# YMH01x.net
KiCad netlist of a schematic drawn in EAGLE
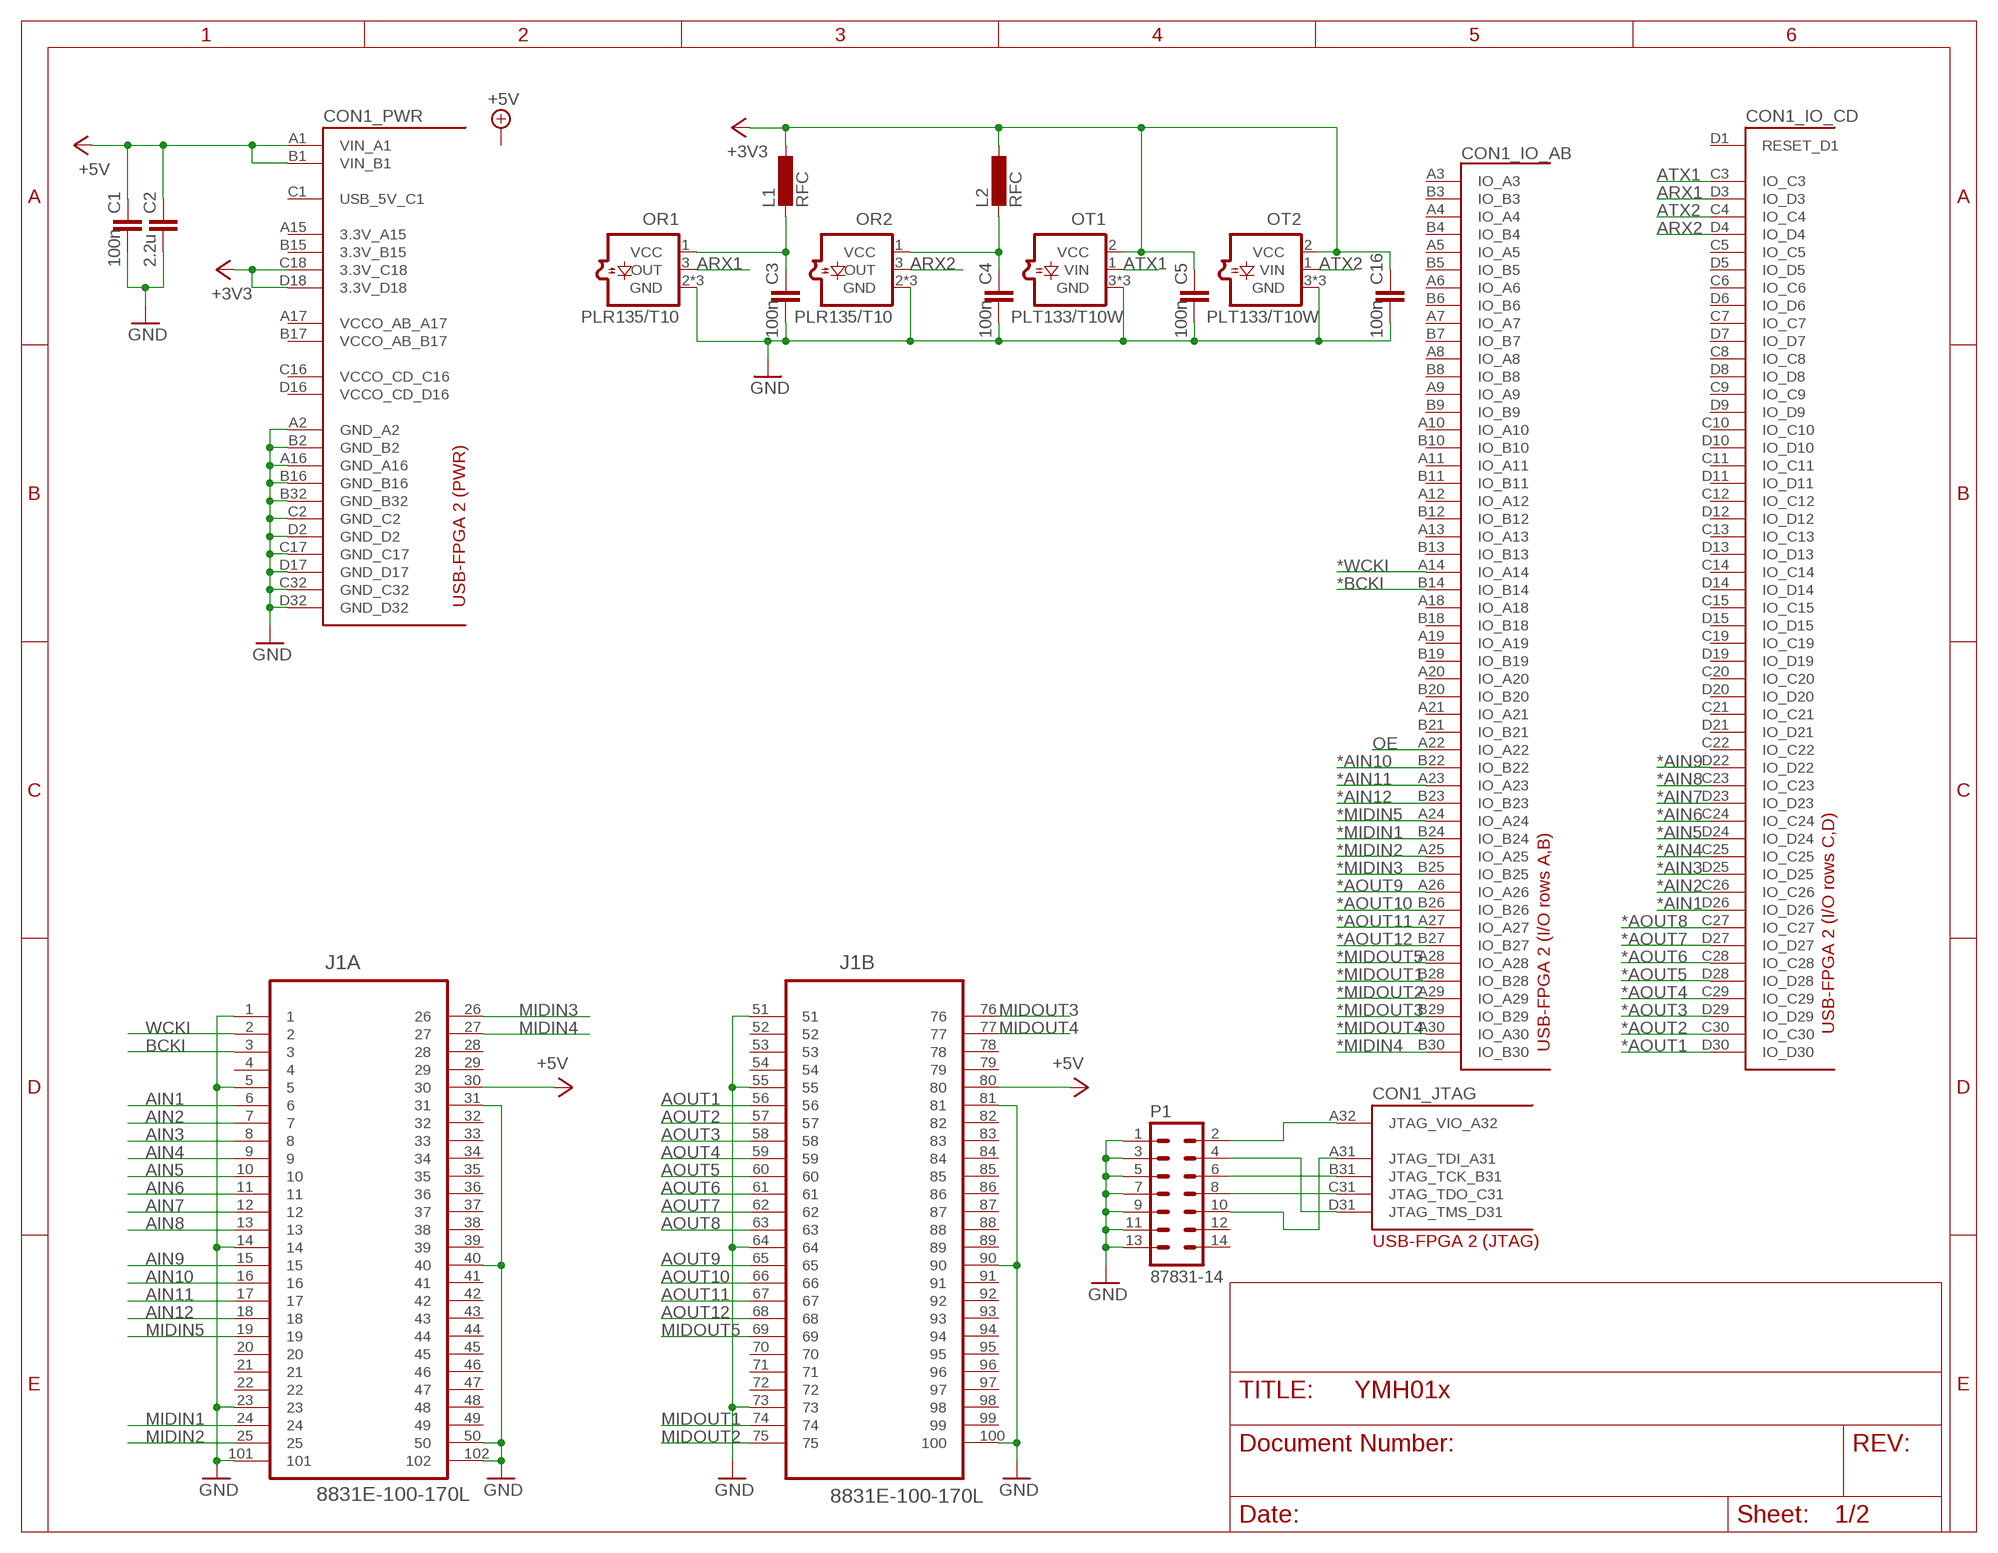
[diagram p0: schematic, sheet 1]
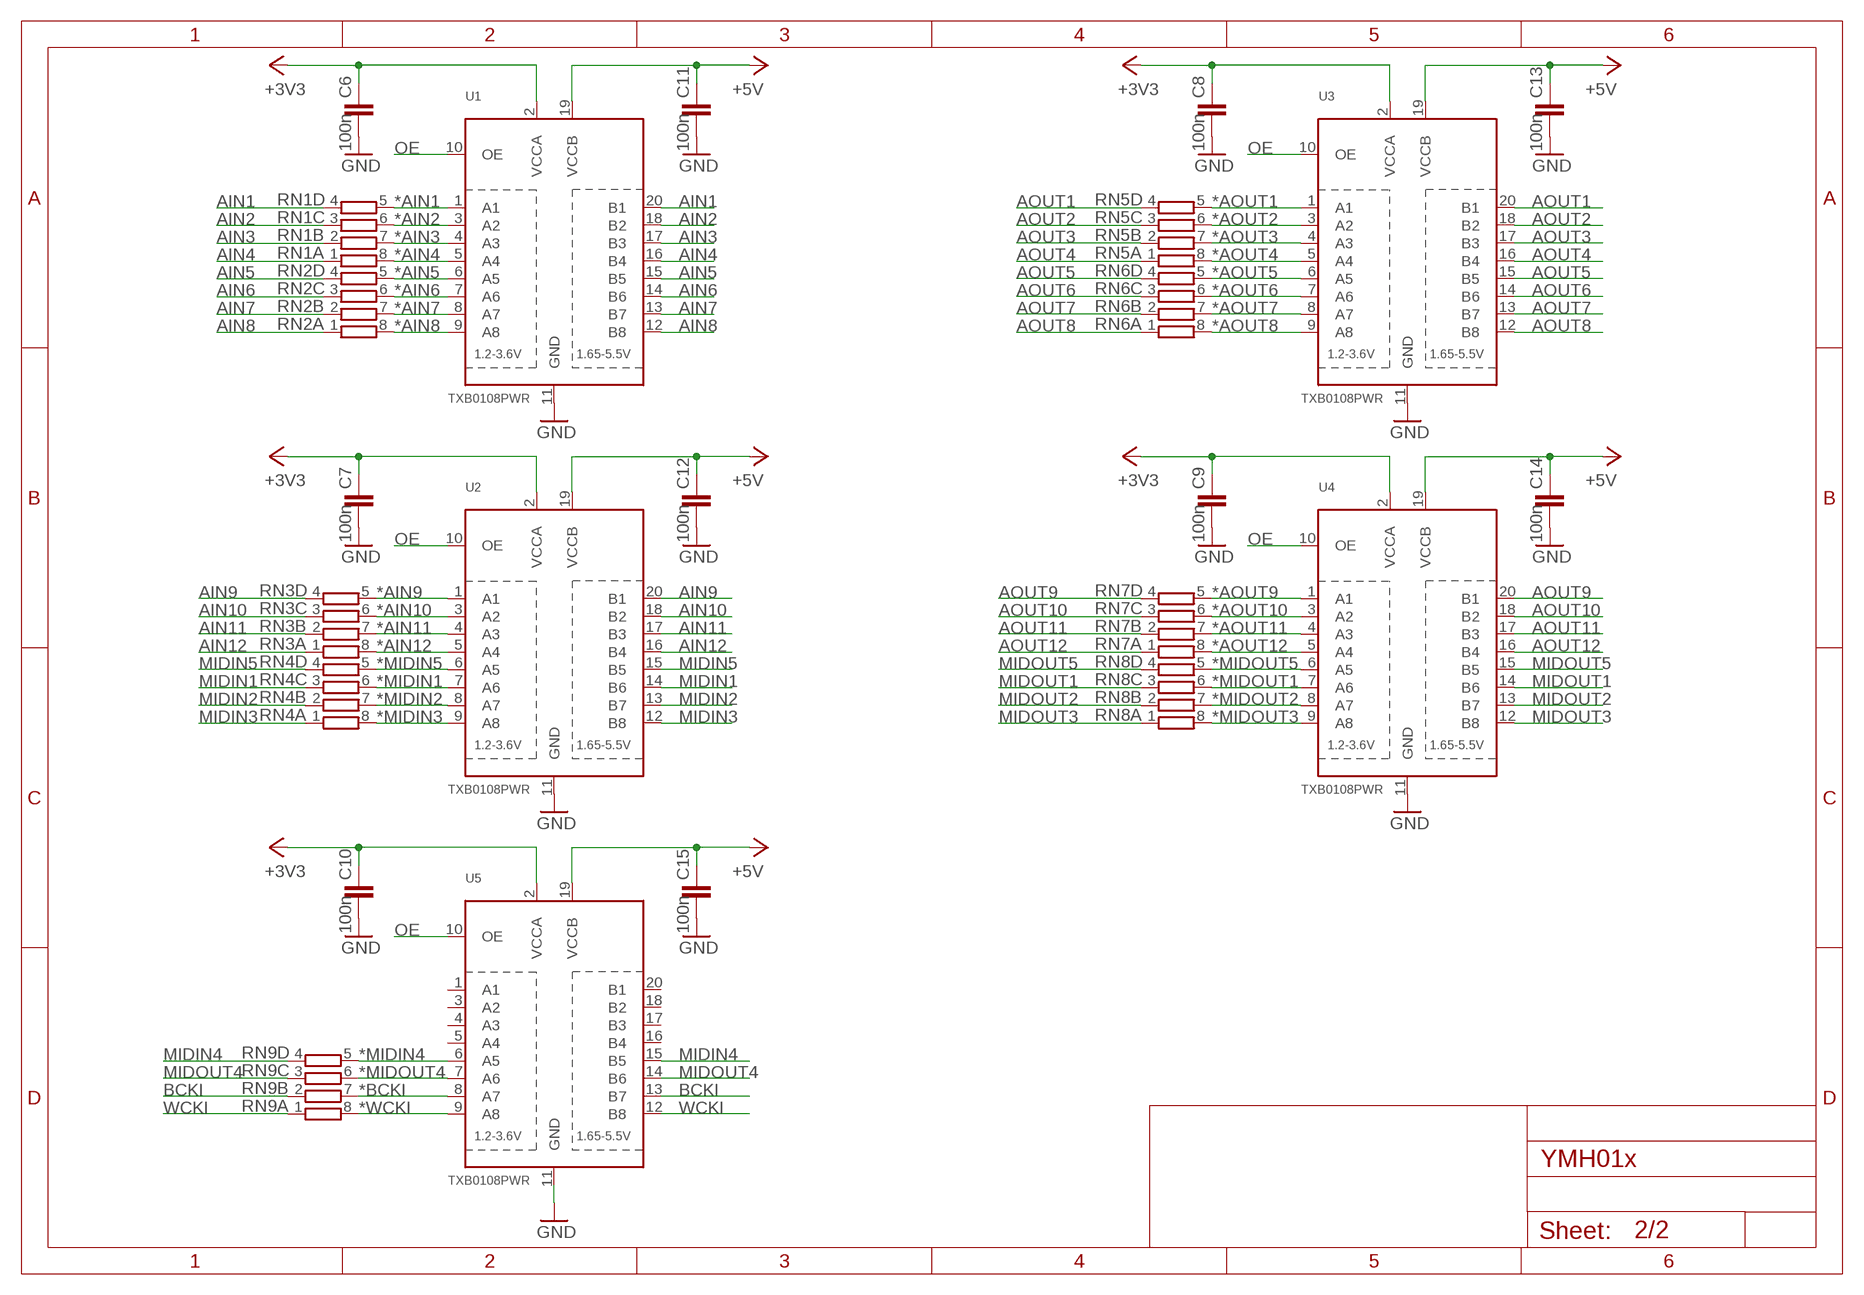
[diagram p1: schematic, sheet 2]

(export (version "E")
  (design (tool "Eeschema 10.0.6"))
  (components
    (comp (ref "C1")
      (value "100n")
      (footprint "eagle-import:C0603")
      (libsource (lib "eagle-import") (part "C-EUC0603"))
    )
    (comp (ref "C2")
      (value "2.2u")
      (footprint "eagle-import:C0603")
      (libsource (lib "eagle-import") (part "C-EUC0603"))
    )
    (comp (ref "C3")
      (value "100n")
      (footprint "eagle-import:C0603")
      (libsource (lib "eagle-import") (part "C-EUC0603"))
    )
    (comp (ref "C4")
      (value "100n")
      (footprint "eagle-import:C0603")
      (libsource (lib "eagle-import") (part "C-EUC0603"))
    )
    (comp (ref "C5")
      (value "100n")
      (footprint "eagle-import:C0603")
      (libsource (lib "eagle-import") (part "C-EUC0603"))
    )
    (comp (ref "C16")
      (value "100n")
      (footprint "eagle-import:C0603")
      (libsource (lib "eagle-import") (part "C-EUC0603"))
    )
    (comp (ref "CON1")
      (value "USB-FPGA-2THT")
      (footprint "eagle-import:USB-FPGA-2-THT")
      (libsource (lib "eagle-import") (part "USB-FPGA-2THT"))
    )
    (comp (ref "J1")
      (value "8831E-100-170L")
      (footprint "eagle-import:KEL_8831E-100-170L")
      (fields (field (name "MPN") "KEL_8831E-100-170L"))
      (libsource (lib "eagle-import") (part "8831E-100-170L"))
    )
    (comp (ref "L1")
      (value "RFC")
      (footprint "eagle-import:L2012C")
      (libsource (lib "eagle-import") (part "L-EUL2012C"))
    )
    (comp (ref "L2")
      (value "RFC")
      (footprint "eagle-import:L2012C")
      (libsource (lib "eagle-import") (part "L-EUL2012C"))
    )
    (comp (ref "OR1")
      (value "PLR135/T10")
      (footprint "eagle-import:PLR135_T10")
      (libsource (lib "eagle-import") (part "PLR135/T10"))
    )
    (comp (ref "OR2")
      (value "PLR135/T10")
      (footprint "eagle-import:PLR135_T10")
      (libsource (lib "eagle-import") (part "PLR135/T10"))
    )
    (comp (ref "OT1")
      (value "PLT133/T10W")
      (footprint "eagle-import:PLT133_T10")
      (libsource (lib "eagle-import") (part "PLT133/T10W"))
    )
    (comp (ref "OT2")
      (value "PLT133/T10W")
      (footprint "eagle-import:PLT133_T10")
      (libsource (lib "eagle-import") (part "PLT133/T10W"))
    )
    (comp (ref "P1")
      (value "87831-14")
      (footprint "eagle-import:87831-14")
      (libsource (lib "eagle-import") (part "87831-14"))
    )
    (comp (ref "C6")
      (value "100n")
      (footprint "eagle-import:C0603")
      (libsource (lib "eagle-import") (part "C-EUC0603"))
    )
    (comp (ref "C7")
      (value "100n")
      (footprint "eagle-import:C0603")
      (libsource (lib "eagle-import") (part "C-EUC0603"))
    )
    (comp (ref "C8")
      (value "100n")
      (footprint "eagle-import:C0603")
      (libsource (lib "eagle-import") (part "C-EUC0603"))
    )
    (comp (ref "C9")
      (value "100n")
      (footprint "eagle-import:C0603")
      (libsource (lib "eagle-import") (part "C-EUC0603"))
    )
    (comp (ref "C10")
      (value "100n")
      (footprint "eagle-import:C0603")
      (libsource (lib "eagle-import") (part "C-EUC0603"))
    )
    (comp (ref "C11")
      (value "100n")
      (footprint "eagle-import:C0603")
      (libsource (lib "eagle-import") (part "C-EUC0603"))
    )
    (comp (ref "C12")
      (value "100n")
      (footprint "eagle-import:C0603")
      (libsource (lib "eagle-import") (part "C-EUC0603"))
    )
    (comp (ref "C13")
      (value "100n")
      (footprint "eagle-import:C0603")
      (libsource (lib "eagle-import") (part "C-EUC0603"))
    )
    (comp (ref "C14")
      (value "100n")
      (footprint "eagle-import:C0603")
      (libsource (lib "eagle-import") (part "C-EUC0603"))
    )
    (comp (ref "C15")
      (value "100n")
      (footprint "eagle-import:C0603")
      (libsource (lib "eagle-import") (part "C-EUC0603"))
    )
    (comp (ref "RN1")
      (value "4R-N0603-ARC")
      (footprint "eagle-import:0603-ARC")
      (libsource (lib "eagle-import") (part "4R-N0603-ARC"))
    )
    (comp (ref "RN2")
      (value "4R-N0603-ARC")
      (footprint "eagle-import:0603-ARC")
      (libsource (lib "eagle-import") (part "4R-N0603-ARC"))
    )
    (comp (ref "RN3")
      (value "4R-N0603-ARC")
      (footprint "eagle-import:0603-ARC")
      (libsource (lib "eagle-import") (part "4R-N0603-ARC"))
    )
    (comp (ref "RN4")
      (value "4R-N0603-ARC")
      (footprint "eagle-import:0603-ARC")
      (libsource (lib "eagle-import") (part "4R-N0603-ARC"))
    )
    (comp (ref "RN5")
      (value "4R-N0603-ARC")
      (footprint "eagle-import:0603-ARC")
      (libsource (lib "eagle-import") (part "4R-N0603-ARC"))
    )
    (comp (ref "RN6")
      (value "4R-N0603-ARC")
      (footprint "eagle-import:0603-ARC")
      (libsource (lib "eagle-import") (part "4R-N0603-ARC"))
    )
    (comp (ref "RN7")
      (value "4R-N0603-ARC")
      (footprint "eagle-import:0603-ARC")
      (libsource (lib "eagle-import") (part "4R-N0603-ARC"))
    )
    (comp (ref "RN8")
      (value "4R-N0603-ARC")
      (footprint "eagle-import:0603-ARC")
      (libsource (lib "eagle-import") (part "4R-N0603-ARC"))
    )
    (comp (ref "RN9")
      (value "4R-N0603-ARC")
      (footprint "eagle-import:0603-ARC")
      (libsource (lib "eagle-import") (part "4R-N0603-ARC"))
    )
    (comp (ref "U1")
      (value "TXB0108PWR")
      (footprint "eagle-import:TSSOP20")
      (libsource (lib "eagle-import") (part "TXB0108PWR"))
    )
    (comp (ref "U2")
      (value "TXB0108PWR")
      (footprint "eagle-import:TSSOP20")
      (libsource (lib "eagle-import") (part "TXB0108PWR"))
    )
    (comp (ref "U3")
      (value "TXB0108PWR")
      (footprint "eagle-import:TSSOP20")
      (libsource (lib "eagle-import") (part "TXB0108PWR"))
    )
    (comp (ref "U4")
      (value "TXB0108PWR")
      (footprint "eagle-import:TSSOP20")
      (libsource (lib "eagle-import") (part "TXB0108PWR"))
    )
    (comp (ref "U5")
      (value "TXB0108PWR")
      (footprint "eagle-import:TSSOP20")
      (libsource (lib "eagle-import") (part "TXB0108PWR"))
    )
  )
  (nets
    (net (code "1") (name "*AIN1") (class "Default")
      (node (ref "CON1") (pin "D26") (pinfunction "IO_D26_D26") (pintype "bidirectional"))
      (node (ref "RN1") (pin "5") (pinfunction "2_5") (pintype "passive"))
      (node (ref "U1") (pin "1") (pinfunction "A1_1") (pintype "bidirectional"))
    )
    (net (code "2") (name "*AIN2") (class "Default")
      (node (ref "CON1") (pin "C26") (pinfunction "IO_C26_C26") (pintype "bidirectional"))
      (node (ref "RN1") (pin "6") (pinfunction "2_6") (pintype "passive"))
      (node (ref "U1") (pin "3") (pinfunction "A2_3") (pintype "bidirectional"))
    )
    (net (code "3") (name "*AIN3") (class "Default")
      (node (ref "CON1") (pin "D25") (pinfunction "IO_D25_D25") (pintype "bidirectional"))
      (node (ref "RN1") (pin "7") (pinfunction "2_7") (pintype "passive"))
      (node (ref "U1") (pin "4") (pinfunction "A3_4") (pintype "bidirectional"))
    )
    (net (code "4") (name "*AIN4") (class "Default")
      (node (ref "CON1") (pin "C25") (pinfunction "IO_C25_C25") (pintype "bidirectional"))
      (node (ref "RN1") (pin "8") (pinfunction "2_8") (pintype "passive"))
      (node (ref "U1") (pin "5") (pinfunction "A4_5") (pintype "bidirectional"))
    )
    (net (code "5") (name "*AIN5") (class "Default")
      (node (ref "CON1") (pin "D24") (pinfunction "IO_D24_D24") (pintype "bidirectional"))
      (node (ref "RN2") (pin "5") (pinfunction "2_5") (pintype "passive"))
      (node (ref "U1") (pin "6") (pinfunction "A5_6") (pintype "bidirectional"))
    )
    (net (code "6") (name "*AIN6") (class "Default")
      (node (ref "CON1") (pin "C24") (pinfunction "IO_C24_C24") (pintype "bidirectional"))
      (node (ref "RN2") (pin "6") (pinfunction "2_6") (pintype "passive"))
      (node (ref "U1") (pin "7") (pinfunction "A6_7") (pintype "bidirectional"))
    )
    (net (code "7") (name "*AIN7") (class "Default")
      (node (ref "CON1") (pin "D23") (pinfunction "IO_D23_D23") (pintype "bidirectional"))
      (node (ref "RN2") (pin "7") (pinfunction "2_7") (pintype "passive"))
      (node (ref "U1") (pin "8") (pinfunction "A7_8") (pintype "bidirectional"))
    )
    (net (code "8") (name "*AIN8") (class "Default")
      (node (ref "CON1") (pin "C23") (pinfunction "IO_C23_C23") (pintype "bidirectional"))
      (node (ref "RN2") (pin "8") (pinfunction "2_8") (pintype "passive"))
      (node (ref "U1") (pin "9") (pinfunction "A8_9") (pintype "bidirectional"))
    )
    (net (code "9") (name "*AIN9") (class "Default")
      (node (ref "CON1") (pin "D22") (pinfunction "IO_D22_D22") (pintype "bidirectional"))
      (node (ref "RN3") (pin "5") (pinfunction "2_5") (pintype "passive"))
      (node (ref "U2") (pin "1") (pinfunction "A1_1") (pintype "bidirectional"))
    )
    (net (code "10") (name "*AIN10") (class "Default")
      (node (ref "CON1") (pin "B22") (pinfunction "IO_B22_B22") (pintype "bidirectional"))
      (node (ref "RN3") (pin "6") (pinfunction "2_6") (pintype "passive"))
      (node (ref "U2") (pin "3") (pinfunction "A2_3") (pintype "bidirectional"))
    )
    (net (code "11") (name "*AIN11") (class "Default")
      (node (ref "CON1") (pin "A23") (pinfunction "IO_A23_A23") (pintype "bidirectional"))
      (node (ref "RN3") (pin "7") (pinfunction "2_7") (pintype "passive"))
      (node (ref "U2") (pin "4") (pinfunction "A3_4") (pintype "bidirectional"))
    )
    (net (code "12") (name "*AIN12") (class "Default")
      (node (ref "CON1") (pin "B23") (pinfunction "IO_B23_B23") (pintype "bidirectional"))
      (node (ref "RN3") (pin "8") (pinfunction "2_8") (pintype "passive"))
      (node (ref "U2") (pin "5") (pinfunction "A4_5") (pintype "bidirectional"))
    )
    (net (code "13") (name "*AOUT1") (class "Default")
      (node (ref "CON1") (pin "D30") (pinfunction "IO_D30_D30") (pintype "bidirectional"))
      (node (ref "RN5") (pin "5") (pinfunction "2_5") (pintype "passive"))
      (node (ref "U3") (pin "1") (pinfunction "A1_1") (pintype "bidirectional"))
    )
    (net (code "14") (name "*AOUT2") (class "Default")
      (node (ref "CON1") (pin "C30") (pinfunction "IO_C30_C30") (pintype "bidirectional"))
      (node (ref "RN5") (pin "6") (pinfunction "2_6") (pintype "passive"))
      (node (ref "U3") (pin "3") (pinfunction "A2_3") (pintype "bidirectional"))
    )
    (net (code "15") (name "*AOUT3") (class "Default")
      (node (ref "CON1") (pin "D29") (pinfunction "IO_D29_D29") (pintype "bidirectional"))
      (node (ref "RN5") (pin "7") (pinfunction "2_7") (pintype "passive"))
      (node (ref "U3") (pin "4") (pinfunction "A3_4") (pintype "bidirectional"))
    )
    (net (code "16") (name "*AOUT4") (class "Default")
      (node (ref "CON1") (pin "C29") (pinfunction "IO_C29_C29") (pintype "bidirectional"))
      (node (ref "RN5") (pin "8") (pinfunction "2_8") (pintype "passive"))
      (node (ref "U3") (pin "5") (pinfunction "A4_5") (pintype "bidirectional"))
    )
    (net (code "17") (name "*AOUT5") (class "Default")
      (node (ref "CON1") (pin "D28") (pinfunction "IO_D28_D28") (pintype "bidirectional"))
      (node (ref "RN6") (pin "5") (pinfunction "2_5") (pintype "passive"))
      (node (ref "U3") (pin "6") (pinfunction "A5_6") (pintype "bidirectional"))
    )
    (net (code "18") (name "*AOUT6") (class "Default")
      (node (ref "CON1") (pin "C28") (pinfunction "IO_C28_C28") (pintype "bidirectional"))
      (node (ref "RN6") (pin "6") (pinfunction "2_6") (pintype "passive"))
      (node (ref "U3") (pin "7") (pinfunction "A6_7") (pintype "bidirectional"))
    )
    (net (code "19") (name "*AOUT7") (class "Default")
      (node (ref "CON1") (pin "D27") (pinfunction "IO_D27_D27") (pintype "bidirectional"))
      (node (ref "RN6") (pin "7") (pinfunction "2_7") (pintype "passive"))
      (node (ref "U3") (pin "8") (pinfunction "A7_8") (pintype "bidirectional"))
    )
    (net (code "20") (name "*AOUT8") (class "Default")
      (node (ref "CON1") (pin "C27") (pinfunction "IO_C27_C27") (pintype "bidirectional"))
      (node (ref "RN6") (pin "8") (pinfunction "2_8") (pintype "passive"))
      (node (ref "U3") (pin "9") (pinfunction "A8_9") (pintype "bidirectional"))
    )
    (net (code "21") (name "*AOUT9") (class "Default")
      (node (ref "CON1") (pin "A26") (pinfunction "IO_A26_A26") (pintype "bidirectional"))
      (node (ref "RN7") (pin "5") (pinfunction "2_5") (pintype "passive"))
      (node (ref "U4") (pin "1") (pinfunction "A1_1") (pintype "bidirectional"))
    )
    (net (code "22") (name "*AOUT10") (class "Default")
      (node (ref "CON1") (pin "B26") (pinfunction "IO_B26_B26") (pintype "bidirectional"))
      (node (ref "RN7") (pin "6") (pinfunction "2_6") (pintype "passive"))
      (node (ref "U4") (pin "3") (pinfunction "A2_3") (pintype "bidirectional"))
    )
    (net (code "23") (name "*AOUT11") (class "Default")
      (node (ref "CON1") (pin "A27") (pinfunction "IO_A27_A27") (pintype "bidirectional"))
      (node (ref "RN7") (pin "7") (pinfunction "2_7") (pintype "passive"))
      (node (ref "U4") (pin "4") (pinfunction "A3_4") (pintype "bidirectional"))
    )
    (net (code "24") (name "*AOUT12") (class "Default")
      (node (ref "CON1") (pin "B27") (pinfunction "IO_B27_B27") (pintype "bidirectional"))
      (node (ref "RN7") (pin "8") (pinfunction "2_8") (pintype "passive"))
      (node (ref "U4") (pin "5") (pinfunction "A4_5") (pintype "bidirectional"))
    )
    (net (code "25") (name "*BCKI") (class "Default")
      (node (ref "CON1") (pin "B14") (pinfunction "IO_B14_B14") (pintype "bidirectional"))
      (node (ref "RN9") (pin "7") (pinfunction "2_7") (pintype "passive"))
      (node (ref "U5") (pin "8") (pinfunction "A7_8") (pintype "bidirectional"))
    )
    (net (code "26") (name "*MIDIN1") (class "Default")
      (node (ref "CON1") (pin "B24") (pinfunction "IO_B24_B24") (pintype "bidirectional"))
      (node (ref "RN4") (pin "6") (pinfunction "2_6") (pintype "passive"))
      (node (ref "U2") (pin "7") (pinfunction "A6_7") (pintype "bidirectional"))
    )
    (net (code "27") (name "*MIDIN2") (class "Default")
      (node (ref "CON1") (pin "A25") (pinfunction "IO_A25_A25") (pintype "bidirectional"))
      (node (ref "RN4") (pin "7") (pinfunction "2_7") (pintype "passive"))
      (node (ref "U2") (pin "8") (pinfunction "A7_8") (pintype "bidirectional"))
    )
    (net (code "28") (name "*MIDIN3") (class "Default")
      (node (ref "CON1") (pin "B25") (pinfunction "IO_B25_B25") (pintype "bidirectional"))
      (node (ref "RN4") (pin "8") (pinfunction "2_8") (pintype "passive"))
      (node (ref "U2") (pin "9") (pinfunction "A8_9") (pintype "bidirectional"))
    )
    (net (code "29") (name "*MIDIN4") (class "Default")
      (node (ref "CON1") (pin "B30") (pinfunction "IO_B30_B30") (pintype "bidirectional"))
      (node (ref "RN9") (pin "5") (pinfunction "2_5") (pintype "passive"))
      (node (ref "U5") (pin "6") (pinfunction "A5_6") (pintype "bidirectional"))
    )
    (net (code "30") (name "*MIDIN5") (class "Default")
      (node (ref "CON1") (pin "A24") (pinfunction "IO_A24_A24") (pintype "bidirectional"))
      (node (ref "RN4") (pin "5") (pinfunction "2_5") (pintype "passive"))
      (node (ref "U2") (pin "6") (pinfunction "A5_6") (pintype "bidirectional"))
    )
    (net (code "31") (name "*MIDOUT1") (class "Default")
      (node (ref "CON1") (pin "B28") (pinfunction "IO_B28_B28") (pintype "bidirectional"))
      (node (ref "RN8") (pin "6") (pinfunction "2_6") (pintype "passive"))
      (node (ref "U4") (pin "7") (pinfunction "A6_7") (pintype "bidirectional"))
    )
    (net (code "32") (name "*MIDOUT2") (class "Default")
      (node (ref "CON1") (pin "A29") (pinfunction "IO_A29_A29") (pintype "bidirectional"))
      (node (ref "RN8") (pin "7") (pinfunction "2_7") (pintype "passive"))
      (node (ref "U4") (pin "8") (pinfunction "A7_8") (pintype "bidirectional"))
    )
    (net (code "33") (name "*MIDOUT3") (class "Default")
      (node (ref "CON1") (pin "B29") (pinfunction "IO_B29_B29") (pintype "bidirectional"))
      (node (ref "RN8") (pin "8") (pinfunction "2_8") (pintype "passive"))
      (node (ref "U4") (pin "9") (pinfunction "A8_9") (pintype "bidirectional"))
    )
    (net (code "34") (name "*MIDOUT4") (class "Default")
      (node (ref "CON1") (pin "A30") (pinfunction "IO_A30_A30") (pintype "bidirectional"))
      (node (ref "RN9") (pin "6") (pinfunction "2_6") (pintype "passive"))
      (node (ref "U5") (pin "7") (pinfunction "A6_7") (pintype "bidirectional"))
    )
    (net (code "35") (name "*MIDOUT5") (class "Default")
      (node (ref "CON1") (pin "A28") (pinfunction "IO_A28_A28") (pintype "bidirectional"))
      (node (ref "RN8") (pin "5") (pinfunction "2_5") (pintype "passive"))
      (node (ref "U4") (pin "6") (pinfunction "A5_6") (pintype "bidirectional"))
    )
    (net (code "36") (name "*WCKI") (class "Default")
      (node (ref "CON1") (pin "A14") (pinfunction "IO_A14_A14") (pintype "bidirectional"))
      (node (ref "RN9") (pin "8") (pinfunction "2_8") (pintype "passive"))
      (node (ref "U5") (pin "9") (pinfunction "A8_9") (pintype "bidirectional"))
    )
    (net (code "37") (name "+3V3") (class "Default")
      (node (ref "C10") (pin "1") (pinfunction "1_1") (pintype "passive"))
      (node (ref "C16") (pin "1") (pinfunction "1_1") (pintype "passive"))
      (node (ref "C5") (pin "1") (pinfunction "1_1") (pintype "passive"))
      (node (ref "C6") (pin "1") (pinfunction "1_1") (pintype "passive"))
      (node (ref "C7") (pin "1") (pinfunction "1_1") (pintype "passive"))
      (node (ref "C8") (pin "1") (pinfunction "1_1") (pintype "passive"))
      (node (ref "C9") (pin "1") (pinfunction "1_1") (pintype "passive"))
      (node (ref "CON1") (pin "C18") (pinfunction "3.3V_C18_C18") (pintype "bidirectional"))
      (node (ref "CON1") (pin "D18") (pinfunction "3.3V_D18_D18") (pintype "bidirectional"))
      (node (ref "L1") (pin "1") (pinfunction "1_1") (pintype "passive"))
      (node (ref "L2") (pin "1") (pinfunction "1_1") (pintype "passive"))
      (node (ref "OT1") (pin "2") (pinfunction "VCC_2") (pintype "power_in"))
      (node (ref "OT2") (pin "2") (pinfunction "VCC_2") (pintype "power_in"))
      (node (ref "U1") (pin "2") (pinfunction "VCCA_2") (pintype "bidirectional"))
      (node (ref "U2") (pin "2") (pinfunction "VCCA_2") (pintype "bidirectional"))
      (node (ref "U3") (pin "2") (pinfunction "VCCA_2") (pintype "bidirectional"))
      (node (ref "U4") (pin "2") (pinfunction "VCCA_2") (pintype "bidirectional"))
      (node (ref "U5") (pin "2") (pinfunction "VCCA_2") (pintype "bidirectional"))
    )
    (net (code "38") (name "+5V") (class "Default")
      (node (ref "C1") (pin "1") (pinfunction "1_1") (pintype "passive"))
      (node (ref "C11") (pin "1") (pinfunction "1_1") (pintype "passive"))
      (node (ref "C12") (pin "1") (pinfunction "1_1") (pintype "passive"))
      (node (ref "C13") (pin "1") (pinfunction "1_1") (pintype "passive"))
      (node (ref "C14") (pin "1") (pinfunction "1_1") (pintype "passive"))
      (node (ref "C15") (pin "1") (pinfunction "1_1") (pintype "passive"))
      (node (ref "C2") (pin "1") (pinfunction "1_1") (pintype "passive"))
      (node (ref "CON1") (pin "A1") (pinfunction "VIN_A1_A1") (pintype "bidirectional"))
      (node (ref "CON1") (pin "B1") (pinfunction "VIN_B1_B1") (pintype "bidirectional"))
      (node (ref "J1") (pin "30") (pinfunction "30_30") (pintype "passive"))
      (node (ref "J1") (pin "80") (pinfunction "80_80") (pintype "passive"))
      (node (ref "U1") (pin "19") (pinfunction "VCCB_19") (pintype "bidirectional"))
      (node (ref "U2") (pin "19") (pinfunction "VCCB_19") (pintype "bidirectional"))
      (node (ref "U3") (pin "19") (pinfunction "VCCB_19") (pintype "bidirectional"))
      (node (ref "U4") (pin "19") (pinfunction "VCCB_19") (pintype "bidirectional"))
      (node (ref "U5") (pin "19") (pinfunction "VCCB_19") (pintype "bidirectional"))
    )
    (net (code "39") (name "AIN1") (class "Default")
      (node (ref "J1") (pin "6") (pinfunction "6_6") (pintype "passive"))
      (node (ref "RN1") (pin "4") (pinfunction "1_4") (pintype "passive"))
      (node (ref "U1") (pin "20") (pinfunction "B1_20") (pintype "bidirectional"))
    )
    (net (code "40") (name "AIN2") (class "Default")
      (node (ref "J1") (pin "7") (pinfunction "7_7") (pintype "passive"))
      (node (ref "RN1") (pin "3") (pinfunction "1_3") (pintype "passive"))
      (node (ref "U1") (pin "18") (pinfunction "B2_18") (pintype "bidirectional"))
    )
    (net (code "41") (name "AIN3") (class "Default")
      (node (ref "J1") (pin "8") (pinfunction "8_8") (pintype "passive"))
      (node (ref "RN1") (pin "2") (pinfunction "1_2") (pintype "passive"))
      (node (ref "U1") (pin "17") (pinfunction "B3_17") (pintype "bidirectional"))
    )
    (net (code "42") (name "AIN4") (class "Default")
      (node (ref "J1") (pin "9") (pinfunction "9_9") (pintype "passive"))
      (node (ref "RN1") (pin "1") (pinfunction "1_1") (pintype "passive"))
      (node (ref "U1") (pin "16") (pinfunction "B4_16") (pintype "bidirectional"))
    )
    (net (code "43") (name "AIN5") (class "Default")
      (node (ref "J1") (pin "10") (pinfunction "10_10") (pintype "passive"))
      (node (ref "RN2") (pin "4") (pinfunction "1_4") (pintype "passive"))
      (node (ref "U1") (pin "15") (pinfunction "B5_15") (pintype "bidirectional"))
    )
    (net (code "44") (name "AIN6") (class "Default")
      (node (ref "J1") (pin "11") (pinfunction "11_11") (pintype "passive"))
      (node (ref "RN2") (pin "3") (pinfunction "1_3") (pintype "passive"))
      (node (ref "U1") (pin "14") (pinfunction "B6_14") (pintype "bidirectional"))
    )
    (net (code "45") (name "AIN7") (class "Default")
      (node (ref "J1") (pin "12") (pinfunction "12_12") (pintype "passive"))
      (node (ref "RN2") (pin "2") (pinfunction "1_2") (pintype "passive"))
      (node (ref "U1") (pin "13") (pinfunction "B7_13") (pintype "bidirectional"))
    )
    (net (code "46") (name "AIN8") (class "Default")
      (node (ref "J1") (pin "13") (pinfunction "13_13") (pintype "passive"))
      (node (ref "RN2") (pin "1") (pinfunction "1_1") (pintype "passive"))
      (node (ref "U1") (pin "12") (pinfunction "B8_12") (pintype "bidirectional"))
    )
    (net (code "47") (name "AIN9") (class "Default")
      (node (ref "J1") (pin "15") (pinfunction "15_15") (pintype "passive"))
      (node (ref "RN3") (pin "4") (pinfunction "1_4") (pintype "passive"))
      (node (ref "U2") (pin "20") (pinfunction "B1_20") (pintype "bidirectional"))
    )
    (net (code "48") (name "AIN10") (class "Default")
      (node (ref "J1") (pin "16") (pinfunction "16_16") (pintype "passive"))
      (node (ref "RN3") (pin "3") (pinfunction "1_3") (pintype "passive"))
      (node (ref "U2") (pin "18") (pinfunction "B2_18") (pintype "bidirectional"))
    )
    (net (code "49") (name "AIN11") (class "Default")
      (node (ref "J1") (pin "17") (pinfunction "17_17") (pintype "passive"))
      (node (ref "RN3") (pin "2") (pinfunction "1_2") (pintype "passive"))
      (node (ref "U2") (pin "17") (pinfunction "B3_17") (pintype "bidirectional"))
    )
    (net (code "50") (name "AIN12") (class "Default")
      (node (ref "J1") (pin "18") (pinfunction "18_18") (pintype "passive"))
      (node (ref "RN3") (pin "1") (pinfunction "1_1") (pintype "passive"))
      (node (ref "U2") (pin "16") (pinfunction "B4_16") (pintype "bidirectional"))
    )
    (net (code "51") (name "AOUT1") (class "Default")
      (node (ref "J1") (pin "56") (pinfunction "56_56") (pintype "passive"))
      (node (ref "RN5") (pin "4") (pinfunction "1_4") (pintype "passive"))
      (node (ref "U3") (pin "20") (pinfunction "B1_20") (pintype "bidirectional"))
    )
    (net (code "52") (name "AOUT2") (class "Default")
      (node (ref "J1") (pin "57") (pinfunction "57_57") (pintype "passive"))
      (node (ref "RN5") (pin "3") (pinfunction "1_3") (pintype "passive"))
      (node (ref "U3") (pin "18") (pinfunction "B2_18") (pintype "bidirectional"))
    )
    (net (code "53") (name "AOUT3") (class "Default")
      (node (ref "J1") (pin "58") (pinfunction "58_58") (pintype "passive"))
      (node (ref "RN5") (pin "2") (pinfunction "1_2") (pintype "passive"))
      (node (ref "U3") (pin "17") (pinfunction "B3_17") (pintype "bidirectional"))
    )
    (net (code "54") (name "AOUT4") (class "Default")
      (node (ref "J1") (pin "59") (pinfunction "59_59") (pintype "passive"))
      (node (ref "RN5") (pin "1") (pinfunction "1_1") (pintype "passive"))
      (node (ref "U3") (pin "16") (pinfunction "B4_16") (pintype "bidirectional"))
    )
    (net (code "55") (name "AOUT5") (class "Default")
      (node (ref "J1") (pin "60") (pinfunction "60_60") (pintype "passive"))
      (node (ref "RN6") (pin "4") (pinfunction "1_4") (pintype "passive"))
      (node (ref "U3") (pin "15") (pinfunction "B5_15") (pintype "bidirectional"))
    )
    (net (code "56") (name "AOUT6") (class "Default")
      (node (ref "J1") (pin "61") (pinfunction "61_61") (pintype "passive"))
      (node (ref "RN6") (pin "3") (pinfunction "1_3") (pintype "passive"))
      (node (ref "U3") (pin "14") (pinfunction "B6_14") (pintype "bidirectional"))
    )
    (net (code "57") (name "AOUT7") (class "Default")
      (node (ref "J1") (pin "62") (pinfunction "62_62") (pintype "passive"))
      (node (ref "RN6") (pin "2") (pinfunction "1_2") (pintype "passive"))
      (node (ref "U3") (pin "13") (pinfunction "B7_13") (pintype "bidirectional"))
    )
    (net (code "58") (name "AOUT8") (class "Default")
      (node (ref "J1") (pin "63") (pinfunction "63_63") (pintype "passive"))
      (node (ref "RN6") (pin "1") (pinfunction "1_1") (pintype "passive"))
      (node (ref "U3") (pin "12") (pinfunction "B8_12") (pintype "bidirectional"))
    )
    (net (code "59") (name "AOUT9") (class "Default")
      (node (ref "J1") (pin "65") (pinfunction "65_65") (pintype "passive"))
      (node (ref "RN7") (pin "4") (pinfunction "1_4") (pintype "passive"))
      (node (ref "U4") (pin "20") (pinfunction "B1_20") (pintype "bidirectional"))
    )
    (net (code "60") (name "AOUT10") (class "Default")
      (node (ref "J1") (pin "66") (pinfunction "66_66") (pintype "passive"))
      (node (ref "RN7") (pin "3") (pinfunction "1_3") (pintype "passive"))
      (node (ref "U4") (pin "18") (pinfunction "B2_18") (pintype "bidirectional"))
    )
    (net (code "61") (name "AOUT11") (class "Default")
      (node (ref "J1") (pin "67") (pinfunction "67_67") (pintype "passive"))
      (node (ref "RN7") (pin "2") (pinfunction "1_2") (pintype "passive"))
      (node (ref "U4") (pin "17") (pinfunction "B3_17") (pintype "bidirectional"))
    )
    (net (code "62") (name "AOUT12") (class "Default")
      (node (ref "J1") (pin "68") (pinfunction "68_68") (pintype "passive"))
      (node (ref "RN7") (pin "1") (pinfunction "1_1") (pintype "passive"))
      (node (ref "U4") (pin "16") (pinfunction "B4_16") (pintype "bidirectional"))
    )
    (net (code "63") (name "ARX1") (class "Default")
      (node (ref "CON1") (pin "D3") (pinfunction "IO_D3_D3") (pintype "bidirectional"))
      (node (ref "OR1") (pin "3") (pinfunction "OUT_3") (pintype "output"))
    )
    (net (code "64") (name "ARX2") (class "Default")
      (node (ref "CON1") (pin "D4") (pinfunction "IO_D4_D4") (pintype "bidirectional"))
      (node (ref "OR2") (pin "3") (pinfunction "OUT_3") (pintype "output"))
    )
    (net (code "65") (name "ATX1") (class "Default")
      (node (ref "CON1") (pin "C3") (pinfunction "IO_C3_C3") (pintype "bidirectional"))
      (node (ref "OT1") (pin "1") (pinfunction "VIN_1") (pintype "input"))
    )
    (net (code "66") (name "ATX2") (class "Default")
      (node (ref "CON1") (pin "C4") (pinfunction "IO_C4_C4") (pintype "bidirectional"))
      (node (ref "OT2") (pin "1") (pinfunction "VIN_1") (pintype "input"))
    )
    (net (code "67") (name "BCKI") (class "Default")
      (node (ref "J1") (pin "3") (pinfunction "3_3") (pintype "passive"))
      (node (ref "RN9") (pin "2") (pinfunction "1_2") (pintype "passive"))
      (node (ref "U5") (pin "13") (pinfunction "B7_13") (pintype "bidirectional"))
    )
    (net (code "68") (name "GND") (class "Default")
      (node (ref "C1") (pin "2") (pinfunction "2_2") (pintype "passive"))
      (node (ref "C10") (pin "2") (pinfunction "2_2") (pintype "passive"))
      (node (ref "C11") (pin "2") (pinfunction "2_2") (pintype "passive"))
      (node (ref "C12") (pin "2") (pinfunction "2_2") (pintype "passive"))
      (node (ref "C13") (pin "2") (pinfunction "2_2") (pintype "passive"))
      (node (ref "C14") (pin "2") (pinfunction "2_2") (pintype "passive"))
      (node (ref "C15") (pin "2") (pinfunction "2_2") (pintype "passive"))
      (node (ref "C16") (pin "2") (pinfunction "2_2") (pintype "passive"))
      (node (ref "C2") (pin "2") (pinfunction "2_2") (pintype "passive"))
      (node (ref "C3") (pin "2") (pinfunction "2_2") (pintype "passive"))
      (node (ref "C4") (pin "2") (pinfunction "2_2") (pintype "passive"))
      (node (ref "C5") (pin "2") (pinfunction "2_2") (pintype "passive"))
      (node (ref "C6") (pin "2") (pinfunction "2_2") (pintype "passive"))
      (node (ref "C7") (pin "2") (pinfunction "2_2") (pintype "passive"))
      (node (ref "C8") (pin "2") (pinfunction "2_2") (pintype "passive"))
      (node (ref "C9") (pin "2") (pinfunction "2_2") (pintype "passive"))
      (node (ref "CON1") (pin "A16") (pinfunction "GND_A16_A16") (pintype "bidirectional"))
      (node (ref "CON1") (pin "A2") (pinfunction "GND_A2_A2") (pintype "bidirectional"))
      (node (ref "CON1") (pin "B16") (pinfunction "GND_B16_B16") (pintype "bidirectional"))
      (node (ref "CON1") (pin "B2") (pinfunction "GND_B2_B2") (pintype "bidirectional"))
      (node (ref "CON1") (pin "B32") (pinfunction "GND_B32_B32") (pintype "bidirectional"))
      (node (ref "CON1") (pin "C17") (pinfunction "GND_C17_C17") (pintype "bidirectional"))
      (node (ref "CON1") (pin "C2") (pinfunction "GND_C2_C2") (pintype "bidirectional"))
      (node (ref "CON1") (pin "C32") (pinfunction "GND_C32_C32") (pintype "bidirectional"))
      (node (ref "CON1") (pin "D17") (pinfunction "GND_D17_D17") (pintype "bidirectional"))
      (node (ref "CON1") (pin "D2") (pinfunction "GND_D2_D2") (pintype "bidirectional"))
      (node (ref "CON1") (pin "D32") (pinfunction "GND_D32_D32") (pintype "bidirectional"))
      (node (ref "J1") (pin "1") (pinfunction "1_1") (pintype "passive"))
      (node (ref "J1") (pin "100") (pinfunction "100_100") (pintype "passive"))
      (node (ref "J1") (pin "101") (pinfunction "101_101") (pintype "passive"))
      (node (ref "J1") (pin "102") (pinfunction "102_102") (pintype "passive"))
      (node (ref "J1") (pin "14") (pinfunction "14_14") (pintype "passive"))
      (node (ref "J1") (pin "23") (pinfunction "23_23") (pintype "passive"))
      (node (ref "J1") (pin "31") (pinfunction "31_31") (pintype "passive"))
      (node (ref "J1") (pin "40") (pinfunction "40_40") (pintype "passive"))
      (node (ref "J1") (pin "5") (pinfunction "5_5") (pintype "passive"))
      (node (ref "J1") (pin "50") (pinfunction "50_50") (pintype "passive"))
      (node (ref "J1") (pin "51") (pinfunction "51_51") (pintype "passive"))
      (node (ref "J1") (pin "55") (pinfunction "55_55") (pintype "passive"))
      (node (ref "J1") (pin "64") (pinfunction "64_64") (pintype "passive"))
      (node (ref "J1") (pin "73") (pinfunction "73_73") (pintype "passive"))
      (node (ref "J1") (pin "81") (pinfunction "81_81") (pintype "passive"))
      (node (ref "J1") (pin "90") (pinfunction "90_90") (pintype "passive"))
      (node (ref "OR1") (pin "2") (pinfunction "GND_2") (pintype "power_in"))
      (node (ref "OR1") (pin "NC1") (pinfunction "GND_NC1") (pintype "power_in"))
      (node (ref "OR1") (pin "NC2") (pinfunction "GND_NC2") (pintype "power_in"))
      (node (ref "OR2") (pin "2") (pinfunction "GND_2") (pintype "power_in"))
      (node (ref "OR2") (pin "NC1") (pinfunction "GND_NC1") (pintype "power_in"))
      (node (ref "OR2") (pin "NC2") (pinfunction "GND_NC2") (pintype "power_in"))
      (node (ref "OT1") (pin "3") (pinfunction "GND_3") (pintype "power_in"))
      (node (ref "OT1") (pin "NC1") (pinfunction "GND_NC1") (pintype "power_in"))
      (node (ref "OT1") (pin "NC2") (pinfunction "GND_NC2") (pintype "power_in"))
      (node (ref "OT2") (pin "3") (pinfunction "GND_3") (pintype "power_in"))
      (node (ref "OT2") (pin "NC1") (pinfunction "GND_NC1") (pintype "power_in"))
      (node (ref "OT2") (pin "NC2") (pinfunction "GND_NC2") (pintype "power_in"))
      (node (ref "P1") (pin "1") (pinfunction "1_1") (pintype "passive"))
      (node (ref "P1") (pin "11") (pinfunction "11_11") (pintype "passive"))
      (node (ref "P1") (pin "13") (pinfunction "13_13") (pintype "passive"))
      (node (ref "P1") (pin "3") (pinfunction "3_3") (pintype "passive"))
      (node (ref "P1") (pin "5") (pinfunction "5_5") (pintype "passive"))
      (node (ref "P1") (pin "7") (pinfunction "7_7") (pintype "passive"))
      (node (ref "P1") (pin "9") (pinfunction "9_9") (pintype "passive"))
      (node (ref "U1") (pin "11") (pinfunction "GND_11") (pintype "bidirectional"))
      (node (ref "U2") (pin "11") (pinfunction "GND_11") (pintype "bidirectional"))
      (node (ref "U3") (pin "11") (pinfunction "GND_11") (pintype "bidirectional"))
      (node (ref "U4") (pin "11") (pinfunction "GND_11") (pintype "bidirectional"))
      (node (ref "U5") (pin "11") (pinfunction "GND_11") (pintype "bidirectional"))
    )
    (net (code "69") (name "MIDIN1") (class "Default")
      (node (ref "J1") (pin "24") (pinfunction "24_24") (pintype "passive"))
      (node (ref "RN4") (pin "3") (pinfunction "1_3") (pintype "passive"))
      (node (ref "U2") (pin "14") (pinfunction "B6_14") (pintype "bidirectional"))
    )
    (net (code "70") (name "MIDIN2") (class "Default")
      (node (ref "J1") (pin "25") (pinfunction "25_25") (pintype "passive"))
      (node (ref "RN4") (pin "2") (pinfunction "1_2") (pintype "passive"))
      (node (ref "U2") (pin "13") (pinfunction "B7_13") (pintype "bidirectional"))
    )
    (net (code "71") (name "MIDIN3") (class "Default")
      (node (ref "J1") (pin "26") (pinfunction "26_26") (pintype "passive"))
      (node (ref "RN4") (pin "1") (pinfunction "1_1") (pintype "passive"))
      (node (ref "U2") (pin "12") (pinfunction "B8_12") (pintype "bidirectional"))
    )
    (net (code "72") (name "MIDIN4") (class "Default")
      (node (ref "J1") (pin "27") (pinfunction "27_27") (pintype "passive"))
      (node (ref "RN9") (pin "4") (pinfunction "1_4") (pintype "passive"))
      (node (ref "U5") (pin "15") (pinfunction "B5_15") (pintype "bidirectional"))
    )
    (net (code "73") (name "MIDIN5") (class "Default")
      (node (ref "J1") (pin "19") (pinfunction "19_19") (pintype "passive"))
      (node (ref "RN4") (pin "4") (pinfunction "1_4") (pintype "passive"))
      (node (ref "U2") (pin "15") (pinfunction "B5_15") (pintype "bidirectional"))
    )
    (net (code "74") (name "MIDOUT1") (class "Default")
      (node (ref "J1") (pin "74") (pinfunction "74_74") (pintype "passive"))
      (node (ref "RN8") (pin "3") (pinfunction "1_3") (pintype "passive"))
      (node (ref "U4") (pin "14") (pinfunction "B6_14") (pintype "bidirectional"))
    )
    (net (code "75") (name "MIDOUT2") (class "Default")
      (node (ref "J1") (pin "75") (pinfunction "75_75") (pintype "passive"))
      (node (ref "RN8") (pin "2") (pinfunction "1_2") (pintype "passive"))
      (node (ref "U4") (pin "13") (pinfunction "B7_13") (pintype "bidirectional"))
    )
    (net (code "76") (name "MIDOUT3") (class "Default")
      (node (ref "J1") (pin "76") (pinfunction "76_76") (pintype "passive"))
      (node (ref "RN8") (pin "1") (pinfunction "1_1") (pintype "passive"))
      (node (ref "U4") (pin "12") (pinfunction "B8_12") (pintype "bidirectional"))
    )
    (net (code "77") (name "MIDOUT4") (class "Default")
      (node (ref "J1") (pin "77") (pinfunction "77_77") (pintype "passive"))
      (node (ref "RN9") (pin "3") (pinfunction "1_3") (pintype "passive"))
      (node (ref "U5") (pin "14") (pinfunction "B6_14") (pintype "bidirectional"))
    )
    (net (code "78") (name "MIDOUT5") (class "Default")
      (node (ref "J1") (pin "69") (pinfunction "69_69") (pintype "passive"))
      (node (ref "RN8") (pin "4") (pinfunction "1_4") (pintype "passive"))
      (node (ref "U4") (pin "15") (pinfunction "B5_15") (pintype "bidirectional"))
    )
    (net (code "79") (name "Net-(CON1C-JTAG_TCK_B31)") (class "Default")
      (node (ref "CON1") (pin "B31") (pinfunction "JTAG_TCK_B31_B31") (pintype "bidirectional"))
      (node (ref "P1") (pin "6") (pinfunction "6_6") (pintype "passive"))
    )
    (net (code "80") (name "Net-(CON1C-JTAG_TDI_A31)") (class "Default")
      (node (ref "CON1") (pin "A31") (pinfunction "JTAG_TDI_A31_A31") (pintype "bidirectional"))
      (node (ref "P1") (pin "10") (pinfunction "10_10") (pintype "passive"))
    )
    (net (code "81") (name "Net-(CON1C-JTAG_TDO_C31)") (class "Default")
      (node (ref "CON1") (pin "C31") (pinfunction "JTAG_TDO_C31_C31") (pintype "bidirectional"))
      (node (ref "P1") (pin "8") (pinfunction "8_8") (pintype "passive"))
    )
    (net (code "82") (name "Net-(CON1C-JTAG_TMS_D31)") (class "Default")
      (node (ref "CON1") (pin "D31") (pinfunction "JTAG_TMS_D31_D31") (pintype "bidirectional"))
      (node (ref "P1") (pin "4") (pinfunction "4_4") (pintype "passive"))
    )
    (net (code "83") (name "Net-(CON1C-JTAG_VIO_A32)") (class "Default")
      (node (ref "CON1") (pin "A32") (pinfunction "JTAG_VIO_A32_A32") (pintype "bidirectional"))
      (node (ref "P1") (pin "2") (pinfunction "2_2") (pintype "passive"))
    )
    (net (code "84") (name "Net-(OR1-VCC)") (class "Default")
      (node (ref "C3") (pin "1") (pinfunction "1_1") (pintype "passive"))
      (node (ref "L1") (pin "2") (pinfunction "2_2") (pintype "passive"))
      (node (ref "OR1") (pin "1") (pinfunction "VCC_1") (pintype "power_in"))
    )
    (net (code "85") (name "Net-(OR2-VCC)") (class "Default")
      (node (ref "C4") (pin "1") (pinfunction "1_1") (pintype "passive"))
      (node (ref "L2") (pin "2") (pinfunction "2_2") (pintype "passive"))
      (node (ref "OR2") (pin "1") (pinfunction "VCC_1") (pintype "power_in"))
    )
    (net (code "86") (name "OE") (class "Default")
      (node (ref "CON1") (pin "A22") (pinfunction "IO_A22_A22") (pintype "bidirectional"))
      (node (ref "U1") (pin "10") (pinfunction "OE_10") (pintype "bidirectional"))
      (node (ref "U2") (pin "10") (pinfunction "OE_10") (pintype "bidirectional"))
      (node (ref "U3") (pin "10") (pinfunction "OE_10") (pintype "bidirectional"))
      (node (ref "U4") (pin "10") (pinfunction "OE_10") (pintype "bidirectional"))
      (node (ref "U5") (pin "10") (pinfunction "OE_10") (pintype "bidirectional"))
    )
    (net (code "87") (name "WCKI") (class "Default")
      (node (ref "J1") (pin "2") (pinfunction "2_2") (pintype "passive"))
      (node (ref "RN9") (pin "1") (pinfunction "1_1") (pintype "passive"))
      (node (ref "U5") (pin "12") (pinfunction "B8_12") (pintype "bidirectional"))
    )
    (net (code "88") (name "unconnected-(CON1A-IO_A3-PadA3)") (class "Default")
      (node (ref "CON1") (pin "A3") (pinfunction "IO_A3_A3") (pintype "bidirectional"))
    )
    (net (code "89") (name "unconnected-(CON1A-IO_A4-PadA4)") (class "Default")
      (node (ref "CON1") (pin "A4") (pinfunction "IO_A4_A4") (pintype "bidirectional"))
    )
    (net (code "90") (name "unconnected-(CON1A-IO_A5-PadA5)") (class "Default")
      (node (ref "CON1") (pin "A5") (pinfunction "IO_A5_A5") (pintype "bidirectional"))
    )
    (net (code "91") (name "unconnected-(CON1A-IO_A6-PadA6)") (class "Default")
      (node (ref "CON1") (pin "A6") (pinfunction "IO_A6_A6") (pintype "bidirectional"))
    )
    (net (code "92") (name "unconnected-(CON1A-IO_A7-PadA7)") (class "Default")
      (node (ref "CON1") (pin "A7") (pinfunction "IO_A7_A7") (pintype "bidirectional"))
    )
    (net (code "93") (name "unconnected-(CON1A-IO_A8-PadA8)") (class "Default")
      (node (ref "CON1") (pin "A8") (pinfunction "IO_A8_A8") (pintype "bidirectional"))
    )
    (net (code "94") (name "unconnected-(CON1A-IO_A9-PadA9)") (class "Default")
      (node (ref "CON1") (pin "A9") (pinfunction "IO_A9_A9") (pintype "bidirectional"))
    )
    (net (code "95") (name "unconnected-(CON1A-IO_A10-PadA10)") (class "Default")
      (node (ref "CON1") (pin "A10") (pinfunction "IO_A10_A10") (pintype "bidirectional"))
    )
    (net (code "96") (name "unconnected-(CON1A-IO_A11-PadA11)") (class "Default")
      (node (ref "CON1") (pin "A11") (pinfunction "IO_A11_A11") (pintype "bidirectional"))
    )
    (net (code "97") (name "unconnected-(CON1A-IO_A12-PadA12)") (class "Default")
      (node (ref "CON1") (pin "A12") (pinfunction "IO_A12_A12") (pintype "bidirectional"))
    )
    (net (code "98") (name "unconnected-(CON1A-IO_A13-PadA13)") (class "Default")
      (node (ref "CON1") (pin "A13") (pinfunction "IO_A13_A13") (pintype "bidirectional"))
    )
    (net (code "99") (name "unconnected-(CON1A-IO_A18-PadA18)") (class "Default")
      (node (ref "CON1") (pin "A18") (pinfunction "IO_A18_A18") (pintype "bidirectional"))
    )
    (net (code "100") (name "unconnected-(CON1A-IO_A19-PadA19)") (class "Default")
      (node (ref "CON1") (pin "A19") (pinfunction "IO_A19_A19") (pintype "bidirectional"))
    )
    (net (code "101") (name "unconnected-(CON1A-IO_A20-PadA20)") (class "Default")
      (node (ref "CON1") (pin "A20") (pinfunction "IO_A20_A20") (pintype "bidirectional"))
    )
    (net (code "102") (name "unconnected-(CON1A-IO_A21-PadA21)") (class "Default")
      (node (ref "CON1") (pin "A21") (pinfunction "IO_A21_A21") (pintype "bidirectional"))
    )
    (net (code "103") (name "unconnected-(CON1A-IO_B3-PadB3)") (class "Default")
      (node (ref "CON1") (pin "B3") (pinfunction "IO_B3_B3") (pintype "bidirectional"))
    )
    (net (code "104") (name "unconnected-(CON1A-IO_B4-PadB4)") (class "Default")
      (node (ref "CON1") (pin "B4") (pinfunction "IO_B4_B4") (pintype "bidirectional"))
    )
    (net (code "105") (name "unconnected-(CON1A-IO_B5-PadB5)") (class "Default")
      (node (ref "CON1") (pin "B5") (pinfunction "IO_B5_B5") (pintype "bidirectional"))
    )
    (net (code "106") (name "unconnected-(CON1A-IO_B6-PadB6)") (class "Default")
      (node (ref "CON1") (pin "B6") (pinfunction "IO_B6_B6") (pintype "bidirectional"))
    )
    (net (code "107") (name "unconnected-(CON1A-IO_B7-PadB7)") (class "Default")
      (node (ref "CON1") (pin "B7") (pinfunction "IO_B7_B7") (pintype "bidirectional"))
    )
    (net (code "108") (name "unconnected-(CON1A-IO_B8-PadB8)") (class "Default")
      (node (ref "CON1") (pin "B8") (pinfunction "IO_B8_B8") (pintype "bidirectional"))
    )
    (net (code "109") (name "unconnected-(CON1A-IO_B9-PadB9)") (class "Default")
      (node (ref "CON1") (pin "B9") (pinfunction "IO_B9_B9") (pintype "bidirectional"))
    )
    (net (code "110") (name "unconnected-(CON1A-IO_B10-PadB10)") (class "Default")
      (node (ref "CON1") (pin "B10") (pinfunction "IO_B10_B10") (pintype "bidirectional"))
    )
    (net (code "111") (name "unconnected-(CON1A-IO_B11-PadB11)") (class "Default")
      (node (ref "CON1") (pin "B11") (pinfunction "IO_B11_B11") (pintype "bidirectional"))
    )
    (net (code "112") (name "unconnected-(CON1A-IO_B12-PadB12)") (class "Default")
      (node (ref "CON1") (pin "B12") (pinfunction "IO_B12_B12") (pintype "bidirectional"))
    )
    (net (code "113") (name "unconnected-(CON1A-IO_B13-PadB13)") (class "Default")
      (node (ref "CON1") (pin "B13") (pinfunction "IO_B13_B13") (pintype "bidirectional"))
    )
    (net (code "114") (name "unconnected-(CON1A-IO_B18-PadB18)") (class "Default")
      (node (ref "CON1") (pin "B18") (pinfunction "IO_B18_B18") (pintype "bidirectional"))
    )
    (net (code "115") (name "unconnected-(CON1A-IO_B19-PadB19)") (class "Default")
      (node (ref "CON1") (pin "B19") (pinfunction "IO_B19_B19") (pintype "bidirectional"))
    )
    (net (code "116") (name "unconnected-(CON1A-IO_B20-PadB20)") (class "Default")
      (node (ref "CON1") (pin "B20") (pinfunction "IO_B20_B20") (pintype "bidirectional"))
    )
    (net (code "117") (name "unconnected-(CON1A-IO_B21-PadB21)") (class "Default")
      (node (ref "CON1") (pin "B21") (pinfunction "IO_B21_B21") (pintype "bidirectional"))
    )
    (net (code "118") (name "unconnected-(CON1B-IO_C5-PadC5)") (class "Default")
      (node (ref "CON1") (pin "C5") (pinfunction "IO_C5_C5") (pintype "bidirectional"))
    )
    (net (code "119") (name "unconnected-(CON1B-IO_C6-PadC6)") (class "Default")
      (node (ref "CON1") (pin "C6") (pinfunction "IO_C6_C6") (pintype "bidirectional"))
    )
    (net (code "120") (name "unconnected-(CON1B-IO_C7-PadC7)") (class "Default")
      (node (ref "CON1") (pin "C7") (pinfunction "IO_C7_C7") (pintype "bidirectional"))
    )
    (net (code "121") (name "unconnected-(CON1B-IO_C8-PadC8)") (class "Default")
      (node (ref "CON1") (pin "C8") (pinfunction "IO_C8_C8") (pintype "bidirectional"))
    )
    (net (code "122") (name "unconnected-(CON1B-IO_C9-PadC9)") (class "Default")
      (node (ref "CON1") (pin "C9") (pinfunction "IO_C9_C9") (pintype "bidirectional"))
    )
    (net (code "123") (name "unconnected-(CON1B-IO_C10-PadC10)") (class "Default")
      (node (ref "CON1") (pin "C10") (pinfunction "IO_C10_C10") (pintype "bidirectional"))
    )
    (net (code "124") (name "unconnected-(CON1B-IO_C11-PadC11)") (class "Default")
      (node (ref "CON1") (pin "C11") (pinfunction "IO_C11_C11") (pintype "bidirectional"))
    )
    (net (code "125") (name "unconnected-(CON1B-IO_C12-PadC12)") (class "Default")
      (node (ref "CON1") (pin "C12") (pinfunction "IO_C12_C12") (pintype "bidirectional"))
    )
    (net (code "126") (name "unconnected-(CON1B-IO_C13-PadC13)") (class "Default")
      (node (ref "CON1") (pin "C13") (pinfunction "IO_C13_C13") (pintype "bidirectional"))
    )
    (net (code "127") (name "unconnected-(CON1B-IO_C14-PadC14)") (class "Default")
      (node (ref "CON1") (pin "C14") (pinfunction "IO_C14_C14") (pintype "bidirectional"))
    )
    (net (code "128") (name "unconnected-(CON1B-IO_C15-PadC15)") (class "Default")
      (node (ref "CON1") (pin "C15") (pinfunction "IO_C15_C15") (pintype "bidirectional"))
    )
    (net (code "129") (name "unconnected-(CON1B-IO_C19-PadC19)") (class "Default")
      (node (ref "CON1") (pin "C19") (pinfunction "IO_C19_C19") (pintype "bidirectional"))
    )
    (net (code "130") (name "unconnected-(CON1B-IO_C20-PadC20)") (class "Default")
      (node (ref "CON1") (pin "C20") (pinfunction "IO_C20_C20") (pintype "bidirectional"))
    )
    (net (code "131") (name "unconnected-(CON1B-IO_C21-PadC21)") (class "Default")
      (node (ref "CON1") (pin "C21") (pinfunction "IO_C21_C21") (pintype "bidirectional"))
    )
    (net (code "132") (name "unconnected-(CON1B-IO_C22-PadC22)") (class "Default")
      (node (ref "CON1") (pin "C22") (pinfunction "IO_C22_C22") (pintype "bidirectional"))
    )
    (net (code "133") (name "unconnected-(CON1B-IO_D5-PadD5)") (class "Default")
      (node (ref "CON1") (pin "D5") (pinfunction "IO_D5_D5") (pintype "bidirectional"))
    )
    (net (code "134") (name "unconnected-(CON1B-IO_D6-PadD6)") (class "Default")
      (node (ref "CON1") (pin "D6") (pinfunction "IO_D6_D6") (pintype "bidirectional"))
    )
    (net (code "135") (name "unconnected-(CON1B-IO_D7-PadD7)") (class "Default")
      (node (ref "CON1") (pin "D7") (pinfunction "IO_D7_D7") (pintype "bidirectional"))
    )
    (net (code "136") (name "unconnected-(CON1B-IO_D8-PadD8)") (class "Default")
      (node (ref "CON1") (pin "D8") (pinfunction "IO_D8_D8") (pintype "bidirectional"))
    )
    (net (code "137") (name "unconnected-(CON1B-IO_D9-PadD9)") (class "Default")
      (node (ref "CON1") (pin "D9") (pinfunction "IO_D9_D9") (pintype "bidirectional"))
    )
    (net (code "138") (name "unconnected-(CON1B-IO_D10-PadD10)") (class "Default")
      (node (ref "CON1") (pin "D10") (pinfunction "IO_D10_D10") (pintype "bidirectional"))
    )
    (net (code "139") (name "unconnected-(CON1B-IO_D11-PadD11)") (class "Default")
      (node (ref "CON1") (pin "D11") (pinfunction "IO_D11_D11") (pintype "bidirectional"))
    )
    (net (code "140") (name "unconnected-(CON1B-IO_D12-PadD12)") (class "Default")
      (node (ref "CON1") (pin "D12") (pinfunction "IO_D12_D12") (pintype "bidirectional"))
    )
    (net (code "141") (name "unconnected-(CON1B-IO_D13-PadD13)") (class "Default")
      (node (ref "CON1") (pin "D13") (pinfunction "IO_D13_D13") (pintype "bidirectional"))
    )
    (net (code "142") (name "unconnected-(CON1B-IO_D14-PadD14)") (class "Default")
      (node (ref "CON1") (pin "D14") (pinfunction "IO_D14_D14") (pintype "bidirectional"))
    )
    (net (code "143") (name "unconnected-(CON1B-IO_D15-PadD15)") (class "Default")
      (node (ref "CON1") (pin "D15") (pinfunction "IO_D15_D15") (pintype "bidirectional"))
    )
    (net (code "144") (name "unconnected-(CON1B-IO_D19-PadD19)") (class "Default")
      (node (ref "CON1") (pin "D19") (pinfunction "IO_D19_D19") (pintype "bidirectional"))
    )
    (net (code "145") (name "unconnected-(CON1B-IO_D20-PadD20)") (class "Default")
      (node (ref "CON1") (pin "D20") (pinfunction "IO_D20_D20") (pintype "bidirectional"))
    )
    (net (code "146") (name "unconnected-(CON1B-IO_D21-PadD21)") (class "Default")
      (node (ref "CON1") (pin "D21") (pinfunction "IO_D21_D21") (pintype "bidirectional"))
    )
    (net (code "147") (name "unconnected-(CON1B-RESET_D1-PadD1)") (class "Default")
      (node (ref "CON1") (pin "D1") (pinfunction "RESET_D1_D1") (pintype "bidirectional"))
    )
    (net (code "148") (name "unconnected-(CON1D-3.3V_A15-PadA15)") (class "Default")
      (node (ref "CON1") (pin "A15") (pinfunction "3.3V_A15_A15") (pintype "bidirectional"))
    )
    (net (code "149") (name "unconnected-(CON1D-3.3V_B15-PadB15)") (class "Default")
      (node (ref "CON1") (pin "B15") (pinfunction "3.3V_B15_B15") (pintype "bidirectional"))
    )
    (net (code "150") (name "unconnected-(CON1D-USB_5V_C1-PadC1)") (class "Default")
      (node (ref "CON1") (pin "C1") (pinfunction "USB_5V_C1_C1") (pintype "bidirectional"))
    )
    (net (code "151") (name "unconnected-(CON1D-VCCO_AB_A17-PadA17)") (class "Default")
      (node (ref "CON1") (pin "A17") (pinfunction "VCCO_AB_A17_A17") (pintype "bidirectional"))
    )
    (net (code "152") (name "unconnected-(CON1D-VCCO_AB_B17-PadB17)") (class "Default")
      (node (ref "CON1") (pin "B17") (pinfunction "VCCO_AB_B17_B17") (pintype "bidirectional"))
    )
    (net (code "153") (name "unconnected-(CON1D-VCCO_CD_C16-PadC16)") (class "Default")
      (node (ref "CON1") (pin "C16") (pinfunction "VCCO_CD_C16_C16") (pintype "bidirectional"))
    )
    (net (code "154") (name "unconnected-(CON1D-VCCO_CD_D16-PadD16)") (class "Default")
      (node (ref "CON1") (pin "D16") (pinfunction "VCCO_CD_D16_D16") (pintype "bidirectional"))
    )
    (net (code "155") (name "unconnected-(J1-Pad4)") (class "Default")
      (node (ref "J1") (pin "4") (pinfunction "4_4") (pintype "passive"))
    )
    (net (code "156") (name "unconnected-(J1-Pad20)") (class "Default")
      (node (ref "J1") (pin "20") (pinfunction "20_20") (pintype "passive"))
    )
    (net (code "157") (name "unconnected-(J1-Pad21)") (class "Default")
      (node (ref "J1") (pin "21") (pinfunction "21_21") (pintype "passive"))
    )
    (net (code "158") (name "unconnected-(J1-Pad22)") (class "Default")
      (node (ref "J1") (pin "22") (pinfunction "22_22") (pintype "passive"))
    )
    (net (code "159") (name "unconnected-(J1-Pad28)") (class "Default")
      (node (ref "J1") (pin "28") (pinfunction "28_28") (pintype "passive"))
    )
    (net (code "160") (name "unconnected-(J1-Pad29)") (class "Default")
      (node (ref "J1") (pin "29") (pinfunction "29_29") (pintype "passive"))
    )
    (net (code "161") (name "unconnected-(J1-Pad32)") (class "Default")
      (node (ref "J1") (pin "32") (pinfunction "32_32") (pintype "passive"))
    )
    (net (code "162") (name "unconnected-(J1-Pad33)") (class "Default")
      (node (ref "J1") (pin "33") (pinfunction "33_33") (pintype "passive"))
    )
    (net (code "163") (name "unconnected-(J1-Pad34)") (class "Default")
      (node (ref "J1") (pin "34") (pinfunction "34_34") (pintype "passive"))
    )
    (net (code "164") (name "unconnected-(J1-Pad35)") (class "Default")
      (node (ref "J1") (pin "35") (pinfunction "35_35") (pintype "passive"))
    )
    (net (code "165") (name "unconnected-(J1-Pad36)") (class "Default")
      (node (ref "J1") (pin "36") (pinfunction "36_36") (pintype "passive"))
    )
    (net (code "166") (name "unconnected-(J1-Pad37)") (class "Default")
      (node (ref "J1") (pin "37") (pinfunction "37_37") (pintype "passive"))
    )
    (net (code "167") (name "unconnected-(J1-Pad38)") (class "Default")
      (node (ref "J1") (pin "38") (pinfunction "38_38") (pintype "passive"))
    )
    (net (code "168") (name "unconnected-(J1-Pad39)") (class "Default")
      (node (ref "J1") (pin "39") (pinfunction "39_39") (pintype "passive"))
    )
    (net (code "169") (name "unconnected-(J1-Pad41)") (class "Default")
      (node (ref "J1") (pin "41") (pinfunction "41_41") (pintype "passive"))
    )
    (net (code "170") (name "unconnected-(J1-Pad42)") (class "Default")
      (node (ref "J1") (pin "42") (pinfunction "42_42") (pintype "passive"))
    )
    (net (code "171") (name "unconnected-(J1-Pad43)") (class "Default")
      (node (ref "J1") (pin "43") (pinfunction "43_43") (pintype "passive"))
    )
    (net (code "172") (name "unconnected-(J1-Pad44)") (class "Default")
      (node (ref "J1") (pin "44") (pinfunction "44_44") (pintype "passive"))
    )
    (net (code "173") (name "unconnected-(J1-Pad45)") (class "Default")
      (node (ref "J1") (pin "45") (pinfunction "45_45") (pintype "passive"))
    )
    (net (code "174") (name "unconnected-(J1-Pad46)") (class "Default")
      (node (ref "J1") (pin "46") (pinfunction "46_46") (pintype "passive"))
    )
    (net (code "175") (name "unconnected-(J1-Pad47)") (class "Default")
      (node (ref "J1") (pin "47") (pinfunction "47_47") (pintype "passive"))
    )
    (net (code "176") (name "unconnected-(J1-Pad48)") (class "Default")
      (node (ref "J1") (pin "48") (pinfunction "48_48") (pintype "passive"))
    )
    (net (code "177") (name "unconnected-(J1-Pad49)") (class "Default")
      (node (ref "J1") (pin "49") (pinfunction "49_49") (pintype "passive"))
    )
    (net (code "178") (name "unconnected-(J1-Pad52)") (class "Default")
      (node (ref "J1") (pin "52") (pinfunction "52_52") (pintype "passive"))
    )
    (net (code "179") (name "unconnected-(J1-Pad53)") (class "Default")
      (node (ref "J1") (pin "53") (pinfunction "53_53") (pintype "passive"))
    )
    (net (code "180") (name "unconnected-(J1-Pad54)") (class "Default")
      (node (ref "J1") (pin "54") (pinfunction "54_54") (pintype "passive"))
    )
    (net (code "181") (name "unconnected-(J1-Pad70)") (class "Default")
      (node (ref "J1") (pin "70") (pinfunction "70_70") (pintype "passive"))
    )
    (net (code "182") (name "unconnected-(J1-Pad71)") (class "Default")
      (node (ref "J1") (pin "71") (pinfunction "71_71") (pintype "passive"))
    )
    (net (code "183") (name "unconnected-(J1-Pad72)") (class "Default")
      (node (ref "J1") (pin "72") (pinfunction "72_72") (pintype "passive"))
    )
    (net (code "184") (name "unconnected-(J1-Pad78)") (class "Default")
      (node (ref "J1") (pin "78") (pinfunction "78_78") (pintype "passive"))
    )
    (net (code "185") (name "unconnected-(J1-Pad79)") (class "Default")
      (node (ref "J1") (pin "79") (pinfunction "79_79") (pintype "passive"))
    )
    (net (code "186") (name "unconnected-(J1-Pad82)") (class "Default")
      (node (ref "J1") (pin "82") (pinfunction "82_82") (pintype "passive"))
    )
    (net (code "187") (name "unconnected-(J1-Pad83)") (class "Default")
      (node (ref "J1") (pin "83") (pinfunction "83_83") (pintype "passive"))
    )
    (net (code "188") (name "unconnected-(J1-Pad84)") (class "Default")
      (node (ref "J1") (pin "84") (pinfunction "84_84") (pintype "passive"))
    )
    (net (code "189") (name "unconnected-(J1-Pad85)") (class "Default")
      (node (ref "J1") (pin "85") (pinfunction "85_85") (pintype "passive"))
    )
    (net (code "190") (name "unconnected-(J1-Pad86)") (class "Default")
      (node (ref "J1") (pin "86") (pinfunction "86_86") (pintype "passive"))
    )
    (net (code "191") (name "unconnected-(J1-Pad87)") (class "Default")
      (node (ref "J1") (pin "87") (pinfunction "87_87") (pintype "passive"))
    )
    (net (code "192") (name "unconnected-(J1-Pad88)") (class "Default")
      (node (ref "J1") (pin "88") (pinfunction "88_88") (pintype "passive"))
    )
    (net (code "193") (name "unconnected-(J1-Pad89)") (class "Default")
      (node (ref "J1") (pin "89") (pinfunction "89_89") (pintype "passive"))
    )
    (net (code "194") (name "unconnected-(J1-Pad91)") (class "Default")
      (node (ref "J1") (pin "91") (pinfunction "91_91") (pintype "passive"))
    )
    (net (code "195") (name "unconnected-(J1-Pad92)") (class "Default")
      (node (ref "J1") (pin "92") (pinfunction "92_92") (pintype "passive"))
    )
    (net (code "196") (name "unconnected-(J1-Pad93)") (class "Default")
      (node (ref "J1") (pin "93") (pinfunction "93_93") (pintype "passive"))
    )
    (net (code "197") (name "unconnected-(J1-Pad94)") (class "Default")
      (node (ref "J1") (pin "94") (pinfunction "94_94") (pintype "passive"))
    )
    (net (code "198") (name "unconnected-(J1-Pad95)") (class "Default")
      (node (ref "J1") (pin "95") (pinfunction "95_95") (pintype "passive"))
    )
    (net (code "199") (name "unconnected-(J1-Pad96)") (class "Default")
      (node (ref "J1") (pin "96") (pinfunction "96_96") (pintype "passive"))
    )
    (net (code "200") (name "unconnected-(J1-Pad97)") (class "Default")
      (node (ref "J1") (pin "97") (pinfunction "97_97") (pintype "passive"))
    )
    (net (code "201") (name "unconnected-(J1-Pad98)") (class "Default")
      (node (ref "J1") (pin "98") (pinfunction "98_98") (pintype "passive"))
    )
    (net (code "202") (name "unconnected-(J1-Pad99)") (class "Default")
      (node (ref "J1") (pin "99") (pinfunction "99_99") (pintype "passive"))
    )
    (net (code "203") (name "unconnected-(P1-Pad12)") (class "Default")
      (node (ref "P1") (pin "12") (pinfunction "12_12") (pintype "passive"))
    )
    (net (code "204") (name "unconnected-(P1-Pad14)") (class "Default")
      (node (ref "P1") (pin "14") (pinfunction "14_14") (pintype "passive"))
    )
    (net (code "205") (name "unconnected-(U5-A1-Pad1)") (class "Default")
      (node (ref "U5") (pin "1") (pinfunction "A1_1") (pintype "bidirectional"))
    )
    (net (code "206") (name "unconnected-(U5-A2-Pad3)") (class "Default")
      (node (ref "U5") (pin "3") (pinfunction "A2_3") (pintype "bidirectional"))
    )
    (net (code "207") (name "unconnected-(U5-A3-Pad4)") (class "Default")
      (node (ref "U5") (pin "4") (pinfunction "A3_4") (pintype "bidirectional"))
    )
    (net (code "208") (name "unconnected-(U5-A4-Pad5)") (class "Default")
      (node (ref "U5") (pin "5") (pinfunction "A4_5") (pintype "bidirectional"))
    )
    (net (code "209") (name "unconnected-(U5-B1-Pad20)") (class "Default")
      (node (ref "U5") (pin "20") (pinfunction "B1_20") (pintype "bidirectional"))
    )
    (net (code "210") (name "unconnected-(U5-B2-Pad18)") (class "Default")
      (node (ref "U5") (pin "18") (pinfunction "B2_18") (pintype "bidirectional"))
    )
    (net (code "211") (name "unconnected-(U5-B3-Pad17)") (class "Default")
      (node (ref "U5") (pin "17") (pinfunction "B3_17") (pintype "bidirectional"))
    )
    (net (code "212") (name "unconnected-(U5-B4-Pad16)") (class "Default")
      (node (ref "U5") (pin "16") (pinfunction "B4_16") (pintype "bidirectional"))
    )
  )
)
